# MCU089B_XDS110_MCU.net
KiCad netlist of a schematic drawn in Altium Designer
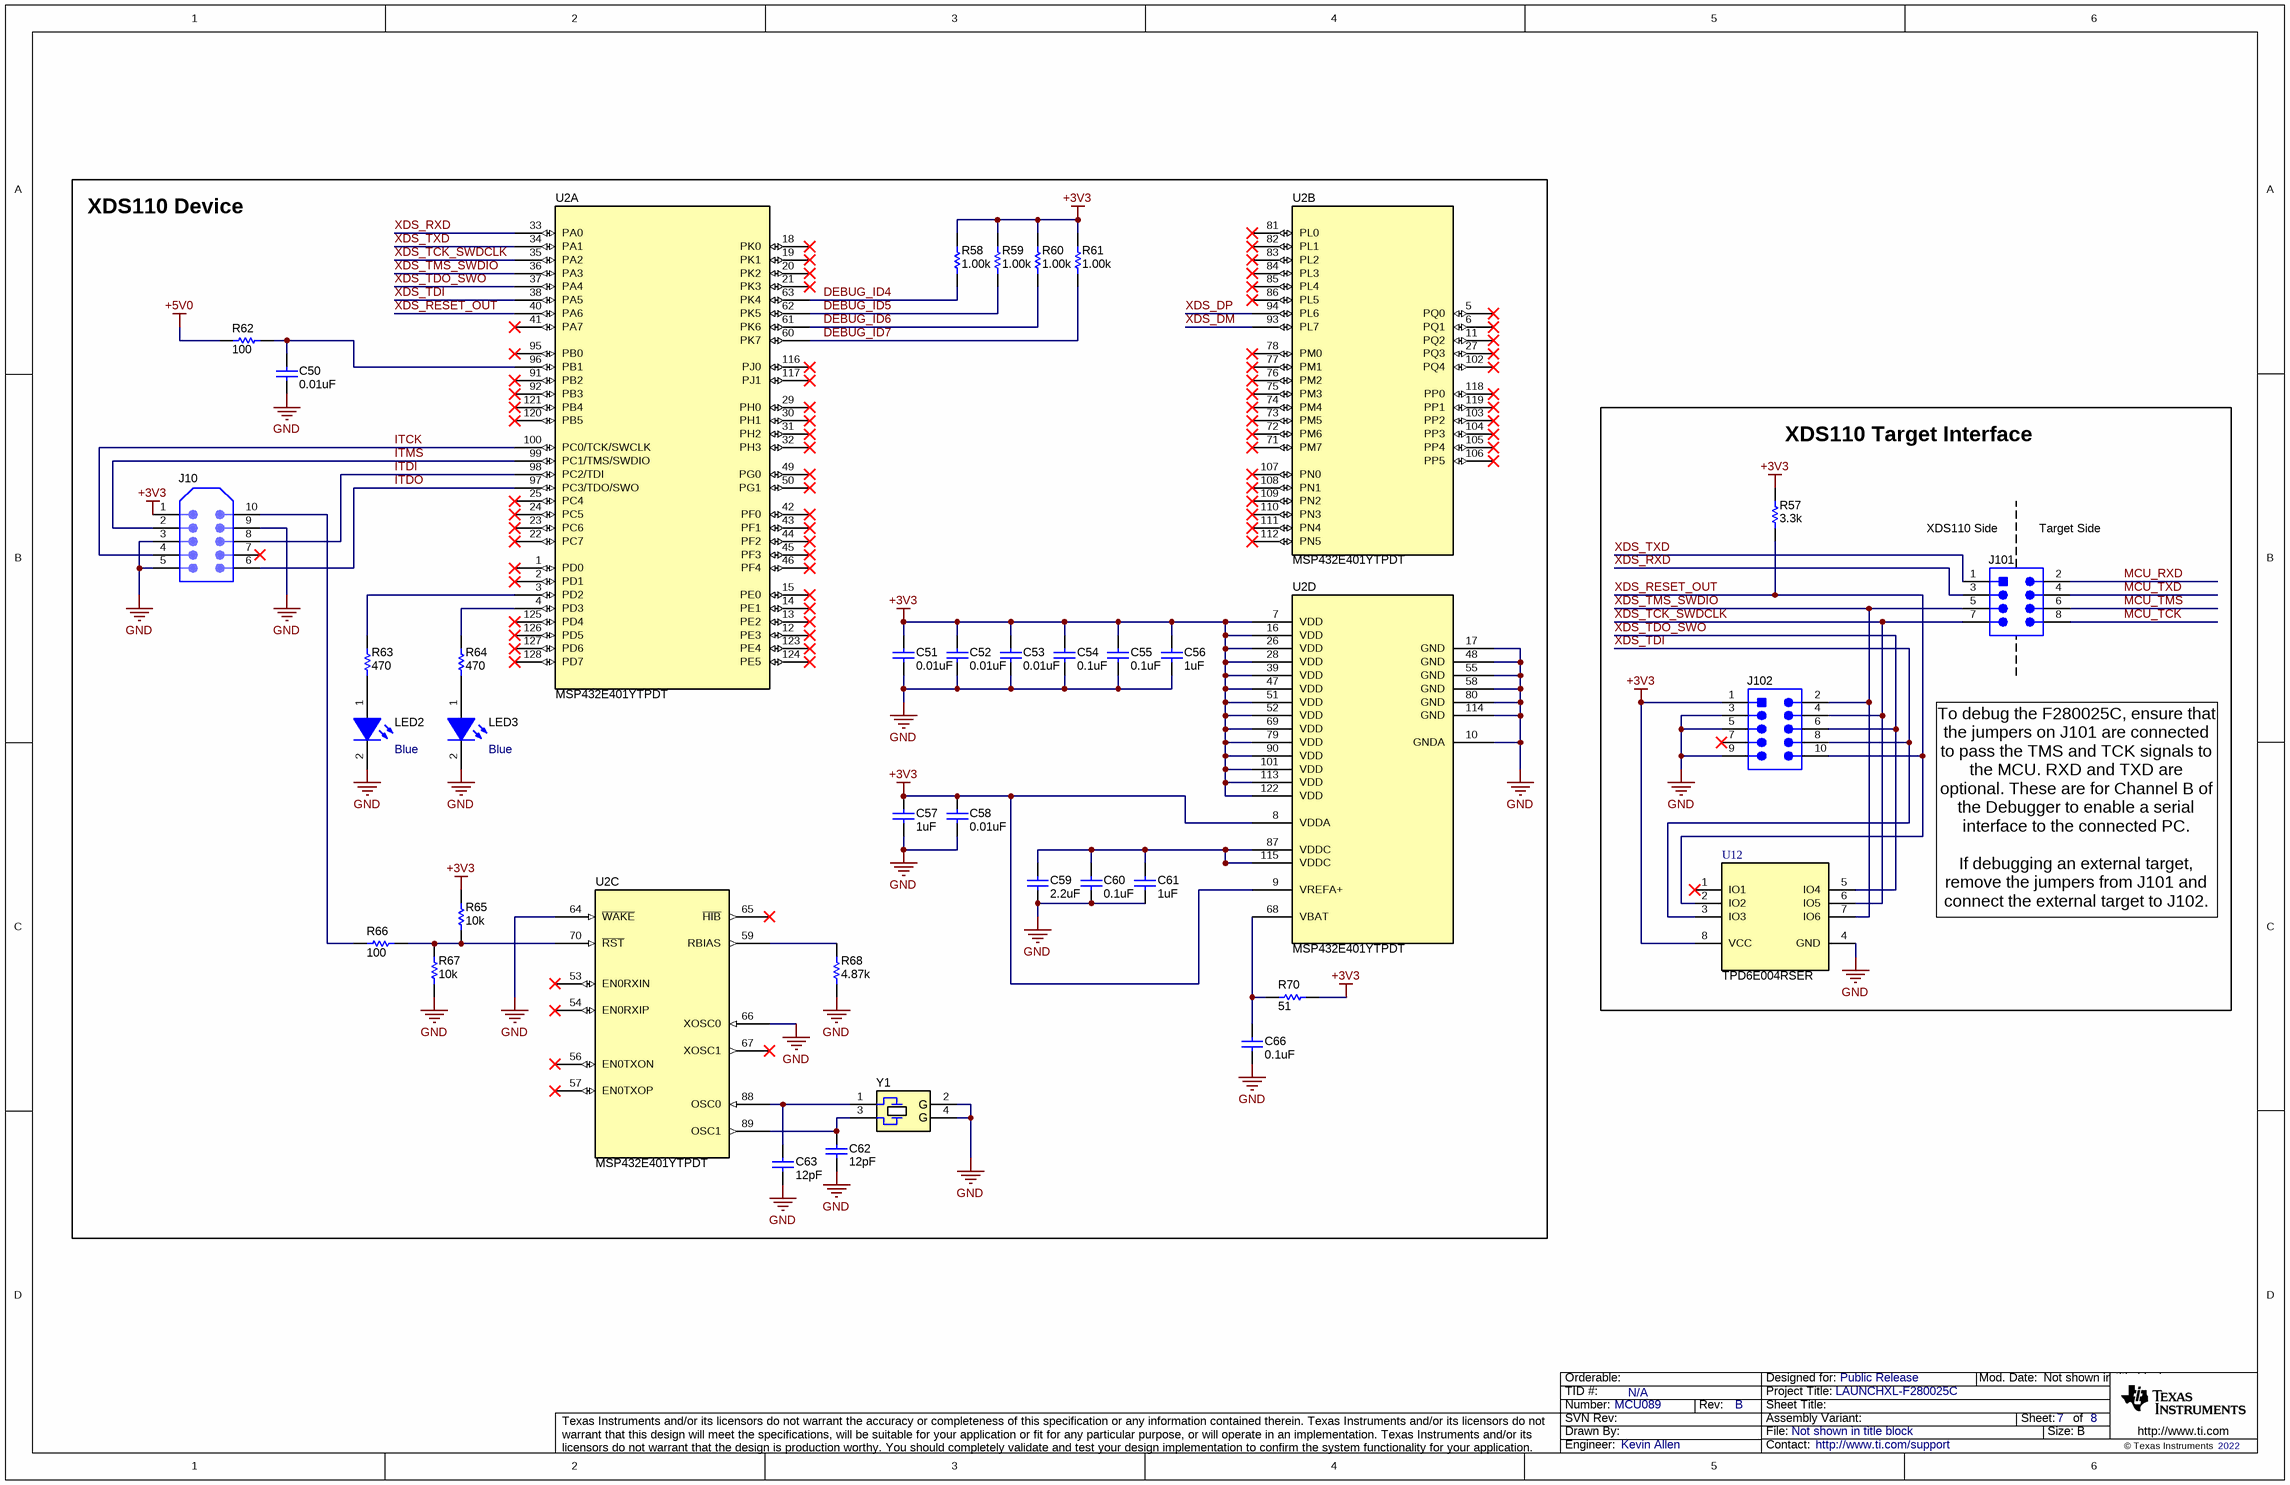
[diagram p0: MCU089B_XDS110_MCU.SchDoc]

(export (version "E")
  (design (tool "Eeschema 10.0.6"))
  (components
    (comp (ref "C50")
      (value "GRM155R71E103KA01D")
      (footprint "0402")
      (description "CAP, CERM, 0.01 uF, 25 V, +/- 10%, X7R, 0402")
      (fields
        (field (name "VALUEDISPLAYED") "0.01uF")
        (field (name "MANUFACTURER") "MuRata")
        (field (name "PUBLISHER") "Texas Instruments")
      )
      (libsource (lib "Altium Vault - TI") (part "Capacitor"))
    )
    (comp (ref "C51")
      (value "GRM155R71E103KA01D")
      (footprint "0402")
      (description "CAP, CERM, 0.01 uF, 25 V, +/- 10%, X7R, 0402")
      (fields
        (field (name "VALUEDISPLAYED") "0.01uF")
        (field (name "MANUFACTURER") "MuRata")
        (field (name "PUBLISHER") "Texas Instruments")
      )
      (libsource (lib "Altium Vault - TI") (part "Capacitor"))
    )
    (comp (ref "C52")
      (value "GRM155R71E103KA01D")
      (footprint "0402")
      (description "CAP, CERM, 0.01 uF, 25 V, +/- 10%, X7R, 0402")
      (fields
        (field (name "VALUEDISPLAYED") "0.01uF")
        (field (name "MANUFACTURER") "MuRata")
        (field (name "PUBLISHER") "Texas Instruments")
      )
      (libsource (lib "Altium Vault - TI") (part "Capacitor"))
    )
    (comp (ref "C53")
      (value "GRM155R71E103KA01D")
      (footprint "0402")
      (description "CAP, CERM, 0.01 uF, 25 V, +/- 10%, X7R, 0402")
      (fields
        (field (name "VALUEDISPLAYED") "0.01uF")
        (field (name "MANUFACTURER") "MuRata")
        (field (name "PUBLISHER") "Texas Instruments")
      )
      (libsource (lib "Altium Vault - TI") (part "Capacitor"))
    )
    (comp (ref "C54")
      (value "GRM155R70J104KA01D")
      (footprint "0402")
      (description "CAP, CERM, 0.1 uF, 6.3 V, +/- 10%, X7R, 0402")
      (fields
        (field (name "VALUEDISPLAYED") "0.1uF")
        (field (name "MANUFACTURER") "MuRata")
        (field (name "PUBLISHER") "Texas Instruments")
      )
      (libsource (lib "Altium Vault - TI") (part "Capacitor"))
    )
    (comp (ref "C55")
      (value "GRM155R70J104KA01D")
      (footprint "0402")
      (description "CAP, CERM, 0.1 uF, 6.3 V, +/- 10%, X7R, 0402")
      (fields
        (field (name "VALUEDISPLAYED") "0.1uF")
        (field (name "MANUFACTURER") "MuRata")
        (field (name "PUBLISHER") "Texas Instruments")
      )
      (libsource (lib "Altium Vault - TI") (part "Capacitor"))
    )
    (comp (ref "C56")
      (value "885012105012")
      (footprint "0402")
      (description "CAP, CERM, 1 uF, 10 V,+/- 20%, X5R, 0402")
      (fields
        (field (name "VALUEDISPLAYED") "1uF")
        (field (name "MANUFACTURER") "Wurth Elektronik")
        (field (name "PUBLISHER") "Texas Instruments")
      )
      (libsource (lib "Altium Vault - TI") (part "Capacitor"))
    )
    (comp (ref "C57")
      (value "885012105012")
      (footprint "0402")
      (description "CAP, CERM, 1 uF, 10 V,+/- 20%, X5R, 0402")
      (fields
        (field (name "VALUEDISPLAYED") "1uF")
        (field (name "MANUFACTURER") "Wurth Elektronik")
        (field (name "PUBLISHER") "Texas Instruments")
      )
      (libsource (lib "Altium Vault - TI") (part "Capacitor"))
    )
    (comp (ref "C58")
      (value "GRM155R71E103KA01D")
      (footprint "0402")
      (description "CAP, CERM, 0.01 uF, 25 V, +/- 10%, X7R, 0402")
      (fields
        (field (name "VALUEDISPLAYED") "0.01uF")
        (field (name "MANUFACTURER") "MuRata")
        (field (name "PUBLISHER") "Texas Instruments")
      )
      (libsource (lib "Altium Vault - TI") (part "Capacitor"))
    )
    (comp (ref "C59")
      (value "GRM155R60J225KE95D")
      (footprint "0402")
      (description "CAP, CERM, 2.2 uF, 6.3 V, +/- 10%, X5R, 0402")
      (fields
        (field (name "VALUEDISPLAYED") "2.2uF")
        (field (name "MANUFACTURER") "MuRata")
        (field (name "PUBLISHER") "Texas Instruments")
      )
      (libsource (lib "Altium Vault - TI") (part "Capacitor"))
    )
    (comp (ref "C60")
      (value "GRM155R70J104KA01D")
      (footprint "0402")
      (description "CAP, CERM, 0.1 uF, 6.3 V, +/- 10%, X7R, 0402")
      (fields
        (field (name "VALUEDISPLAYED") "0.1uF")
        (field (name "MANUFACTURER") "MuRata")
        (field (name "PUBLISHER") "Texas Instruments")
      )
      (libsource (lib "Altium Vault - TI") (part "Capacitor"))
    )
    (comp (ref "C61")
      (value "885012105012")
      (footprint "0402")
      (description "CAP, CERM, 1 uF, 10 V,+/- 20%, X5R, 0402")
      (fields
        (field (name "VALUEDISPLAYED") "1uF")
        (field (name "MANUFACTURER") "Wurth Elektronik")
        (field (name "PUBLISHER") "Texas Instruments")
      )
      (libsource (lib "Altium Vault - TI") (part "Capacitor"))
    )
    (comp (ref "C62")
      (value "C0402C120J3GACAUTO")
      (footprint "0402")
      (description "CAP, CERM, 12 pF, 25 V, +/- 5%, C0G/NP0, AEC-Q200 Grade 1, 0402")
      (fields
        (field (name "MANUFACTURER") "Kemet")
        (field (name "VALUEDISPLAYED") "12pF")
        (field (name "PUBLISHER") "Texas Instruments")
      )
      (libsource (lib "Altium Vault - TI") (part "Capacitor"))
    )
    (comp (ref "C63")
      (value "C0402C120J3GACAUTO")
      (footprint "0402")
      (description "CAP, CERM, 12 pF, 25 V, +/- 5%, C0G/NP0, AEC-Q200 Grade 1, 0402")
      (fields
        (field (name "MANUFACTURER") "Kemet")
        (field (name "VALUEDISPLAYED") "12pF")
        (field (name "PUBLISHER") "Texas Instruments")
      )
      (libsource (lib "Altium Vault - TI") (part "Capacitor"))
    )
    (comp (ref "C66")
      (value "GRM155R70J104KA01D")
      (footprint "0402")
      (description "CAP, CERM, 0.1 uF, 6.3 V, +/- 10%, X7R, 0402")
      (fields
        (field (name "VALUEDISPLAYED") "0.1uF")
        (field (name "MANUFACTURER") "MuRata")
        (field (name "PUBLISHER") "Texas Instruments")
      )
      (libsource (lib "Altium Vault - TI") (part "Capacitor"))
    )
    (comp (ref "J10")
      (value "TC2050-IDC-NL-FP")
      (footprint "Tag_TC2050-NL")
      (description "Footprint for Tag-Connect TC2050 No-Legs cables")
      (fields (field (name "MANUFACTURER") "Tag-Connect") (field (name "PUBLISHER") "Texas Instruments"))
      (libsource (lib "Altium Vault - TI") (part "CMP-0075101-1"))
    )
    (comp (ref "J101")
      (value "TSW-104-07-G-D")
      (footprint "TSW-104-07-G-D")
      (description "Header, 100mil, 4x2, Gold, TH")
      (fields (field (name "MANUFACTURER") "Samtec"))
      (libsource (lib "Altium Vault - TI") (part "Header_4x2"))
    )
    (comp (ref "J102")
      (value "FTSH-105-01-F-DV-K")
      (footprint "Samtec_FTSH-105-01-x-DV-K")
      (description "Header (Shrouded), 1.27mm, 5x2, Gold, SMT")
      (fields (field (name "MANUFACTURER") "Samtec"))
      (libsource (lib "Altium Vault - TI") (part "Header_5x2"))
    )
    (comp (ref "LED2")
      (value "Blue")
      (footprint "LTST-C170TBKT_Blue")
      (description "LED, Blue, SMD")
      (fields (field (name "PARTNUMBER") "LTST-C170TBKT") (field (name "MANUFACTURER") "Lite-On"))
      (libsource (lib "Altium Vault - TI") (part "LED"))
    )
    (comp (ref "LED3")
      (value "Blue")
      (footprint "LTST-C170TBKT_Blue")
      (description "LED, Blue, SMD")
      (fields (field (name "PARTNUMBER") "LTST-C170TBKT") (field (name "MANUFACTURER") "Lite-On"))
      (libsource (lib "Altium Vault - TI") (part "LED"))
    )
    (comp (ref "R57")
      (value "CRCW04023K30JNED")
      (footprint "0402")
      (description "RES, 3.3 k, 5%, 0.063 W, AEC-Q200 Grade 0, 0402")
      (fields (field (name "VALUEDISPLAYED") "3.3k") (field (name "MANUFACTURER") "Vishay-Dale"))
      (libsource (lib "Altium Vault - TI") (part "Resistor"))
    )
    (comp (ref "R58")
      (value "CRCW04021K00FKED")
      (footprint "0402")
      (description "RES, 1.00 k, 1%, 0.063 W, AEC-Q200 Grade 0, 0402")
      (fields (field (name "MANUFACTURER") "Vishay-Dale") (field (name "VALUEDISPLAYED") "1.00k"))
      (libsource (lib "Altium Vault - TI") (part "Resistor"))
    )
    (comp (ref "R59")
      (value "CRCW04021K00FKED")
      (footprint "0402")
      (description "RES, 1.00 k, 1%, 0.063 W, AEC-Q200 Grade 0, 0402")
      (fields (field (name "MANUFACTURER") "Vishay-Dale") (field (name "VALUEDISPLAYED") "1.00k"))
      (libsource (lib "Altium Vault - TI") (part "Resistor"))
    )
    (comp (ref "R60")
      (value "CRCW04021K00FKED")
      (footprint "0402")
      (description "RES, 1.00 k, 1%, 0.063 W, AEC-Q200 Grade 0, 0402")
      (fields (field (name "MANUFACTURER") "Vishay-Dale") (field (name "VALUEDISPLAYED") "1.00k"))
      (libsource (lib "Altium Vault - TI") (part "Resistor"))
    )
    (comp (ref "R61")
      (value "CRCW04021K00FKED")
      (footprint "0402")
      (description "RES, 1.00 k, 1%, 0.063 W, AEC-Q200 Grade 0, 0402")
      (fields (field (name "MANUFACTURER") "Vishay-Dale") (field (name "VALUEDISPLAYED") "1.00k"))
      (libsource (lib "Altium Vault - TI") (part "Resistor"))
    )
    (comp (ref "R62")
      (value "CRCW0402100RJNED")
      (footprint "0402")
      (description "RES, 100, 5%, 0.063 W, AEC-Q200 Grade 0, 0402")
      (fields (field (name "VALUEDISPLAYED") "100") (field (name "MANUFACTURER") "Vishay-Dale"))
      (libsource (lib "Altium Vault - TI") (part "Resistor"))
    )
    (comp (ref "R63")
      (value "ERJ-2RKF4700X")
      (footprint "0402")
      (description "RES, 470, 1%, 0.1 W, AEC-Q200 Grade 0, 0402")
      (fields
        (field (name "VALUEDISPLAYED") "470")
        (field (name "MANUFACTURER") "Panasonic")
        (field (name "PUBLISHER") "Texas Instruments")
      )
      (libsource (lib "Altium Vault - TI") (part "Resistor"))
    )
    (comp (ref "R64")
      (value "ERJ-2RKF4700X")
      (footprint "0402")
      (description "RES, 470, 1%, 0.1 W, AEC-Q200 Grade 0, 0402")
      (fields
        (field (name "VALUEDISPLAYED") "470")
        (field (name "MANUFACTURER") "Panasonic")
        (field (name "PUBLISHER") "Texas Instruments")
      )
      (libsource (lib "Altium Vault - TI") (part "Resistor"))
    )
    (comp (ref "R65")
      (value "CRCW040210K0JNED")
      (footprint "0402")
      (description "RES, 10 k, 5%, 0.063 W, AEC-Q200 Grade 0, 0402")
      (fields (field (name "VALUEDISPLAYED") "10k") (field (name "MANUFACTURER") "Vishay-Dale"))
      (libsource (lib "Altium Vault - TI") (part "Resistor"))
    )
    (comp (ref "R66")
      (value "CRCW0402100RJNED")
      (footprint "0402")
      (description "RES, 100, 5%, 0.063 W, AEC-Q200 Grade 0, 0402")
      (fields (field (name "VALUEDISPLAYED") "100") (field (name "MANUFACTURER") "Vishay-Dale"))
      (libsource (lib "Altium Vault - TI") (part "Resistor"))
    )
    (comp (ref "R67")
      (value "CRCW040210K0JNED")
      (footprint "0402")
      (description "RES, 10 k, 5%, 0.063 W, AEC-Q200 Grade 0, 0402")
      (fields (field (name "VALUEDISPLAYED") "10k") (field (name "MANUFACTURER") "Vishay-Dale"))
      (libsource (lib "Altium Vault - TI") (part "Resistor"))
    )
    (comp (ref "R68")
      (value "CRCW04024K87FKED")
      (footprint "0402")
      (description "RES, 4.87 k, 1%, 0.063 W, AEC-Q200 Grade 0, 0402")
      (fields (field (name "VALUEDISPLAYED") "4.87k") (field (name "MANUFACTURER") "Vishay-Dale"))
      (libsource (lib "Altium Vault - TI") (part "Resistor"))
    )
    (comp (ref "R70")
      (value "CRCW040251R0JNED")
      (footprint "0402")
      (description "RES, 51, 5%, 0.063 W, AEC-Q200 Grade 0, 0402")
      (fields (field (name "VALUEDISPLAYED") "51") (field (name "MANUFACTURER") "Vishay-Dale"))
      (libsource (lib "Altium Vault - TI") (part "Resistor"))
    )
    (comp (ref "U2")
      (value "MSP432E401YTPDT")
      (footprint "PDT0128A")
      (description "MSP432E401YTPDT, PDT0128A (TQFP-128)")
      (fields
        (field (name "ALTERNATE PARTNUMBER") "MSP432E401YTPDTR")
        (field (name "MANUFACTURER") "Texas Instruments")
        (field (name "PARTNUMBER") "MSP432E401YTPDT")
      )
      (libsource (lib "Altium Vault - TI") (part "MSP432E401YTPDT"))
    )
    (comp (ref "U12")
      (value "TPD6E004RSER")
      (footprint "RSE0008A")
      (fields (field (name "MANUFACTURER") "Texas Instruments") (field (name "PARTNUMBER") "TPD6E004RSER"))
      (libsource (lib "Altium Vault - TI") (part "TI-TPD6E004-UQFN_RSE-8"))
    )
    (comp (ref "Y1")
      (value "NX3225GA-16.000M-STD-CRG-1")
      (footprint "NDK_NX3225GA")
      (description "Crystal, 16 MHz, 8pF, SMD")
      (fields (field (name "MANUFACTURER") "NDK"))
      (libsource (lib "Altium Vault - TI") (part "XTAL_4P_13_G24"))
    )
  )
  (nets
    (net (code "1") (name "+3V3") (class "Default")
      (node (ref "C51") (pin "1") (pinfunction "1_1") (pintype "passive"))
      (node (ref "C52") (pin "1") (pinfunction "1_1") (pintype "passive"))
      (node (ref "C53") (pin "1") (pinfunction "1_1") (pintype "passive"))
      (node (ref "C54") (pin "1") (pinfunction "1_1") (pintype "passive"))
      (node (ref "C55") (pin "1") (pinfunction "1_1") (pintype "passive"))
      (node (ref "C56") (pin "1") (pinfunction "1_1") (pintype "passive"))
      (node (ref "C57") (pin "1") (pinfunction "1_1") (pintype "passive"))
      (node (ref "C58") (pin "1") (pinfunction "1_1") (pintype "passive"))
      (node (ref "J10") (pin "1") (pinfunction "1_1") (pintype "passive"))
      (node (ref "J102") (pin "1") (pinfunction "1_1") (pintype "passive"))
      (node (ref "R57") (pin "2") (pinfunction "2_2") (pintype "passive"))
      (node (ref "R58") (pin "2") (pinfunction "2_2") (pintype "passive"))
      (node (ref "R59") (pin "2") (pinfunction "2_2") (pintype "passive"))
      (node (ref "R60") (pin "2") (pinfunction "2_2") (pintype "passive"))
      (node (ref "R61") (pin "2") (pinfunction "2_2") (pintype "passive"))
      (node (ref "R65") (pin "2") (pinfunction "2_2") (pintype "passive"))
      (node (ref "R70") (pin "2") (pinfunction "2_2") (pintype "passive"))
      (node (ref "U12") (pin "8") (pinfunction "VCC_8") (pintype "power_in"))
      (node (ref "U2") (pin "101") (pinfunction "VDD_101") (pintype "power_in"))
      (node (ref "U2") (pin "113") (pinfunction "VDD_113") (pintype "power_in"))
      (node (ref "U2") (pin "122") (pinfunction "VDD_122") (pintype "power_in"))
      (node (ref "U2") (pin "16") (pinfunction "VDD_16") (pintype "power_in"))
      (node (ref "U2") (pin "26") (pinfunction "VDD_26") (pintype "power_in"))
      (node (ref "U2") (pin "28") (pinfunction "VDD_28") (pintype "power_in"))
      (node (ref "U2") (pin "39") (pinfunction "VDD_39") (pintype "power_in"))
      (node (ref "U2") (pin "47") (pinfunction "VDD_47") (pintype "power_in"))
      (node (ref "U2") (pin "51") (pinfunction "VDD_51") (pintype "power_in"))
      (node (ref "U2") (pin "52") (pinfunction "VDD_52") (pintype "power_in"))
      (node (ref "U2") (pin "69") (pinfunction "VDD_69") (pintype "power_in"))
      (node (ref "U2") (pin "7") (pinfunction "VDD_7") (pintype "power_in"))
      (node (ref "U2") (pin "79") (pinfunction "VDD_79") (pintype "power_in"))
      (node (ref "U2") (pin "8") (pinfunction "VDDA_8") (pintype "power_in"))
      (node (ref "U2") (pin "9") (pinfunction "VREFA+_9") (pintype "power_in"))
      (node (ref "U2") (pin "90") (pinfunction "VDD_90") (pintype "power_in"))
    )
    (net (code "2") (name "+5V0") (class "Default")
      (node (ref "R62") (pin "1") (pinfunction "1_1") (pintype "passive"))
    )
    (net (code "3") (name "/DEBUG_ID4") (class "Default")
      (node (ref "R58") (pin "1") (pinfunction "1_1") (pintype "passive"))
      (node (ref "U2") (pin "63") (pinfunction "PK4_63") (pintype "bidirectional"))
    )
    (net (code "4") (name "/DEBUG_ID5") (class "Default")
      (node (ref "R59") (pin "1") (pinfunction "1_1") (pintype "passive"))
      (node (ref "U2") (pin "62") (pinfunction "PK5_62") (pintype "bidirectional"))
    )
    (net (code "5") (name "/DEBUG_ID6") (class "Default")
      (node (ref "R60") (pin "1") (pinfunction "1_1") (pintype "passive"))
      (node (ref "U2") (pin "61") (pinfunction "PK6_61") (pintype "bidirectional"))
    )
    (net (code "6") (name "/DEBUG_ID7") (class "Default")
      (node (ref "R61") (pin "1") (pinfunction "1_1") (pintype "passive"))
      (node (ref "U2") (pin "60") (pinfunction "PK7_60") (pintype "bidirectional"))
    )
    (net (code "7") (name "/ITCK") (class "Default")
      (node (ref "J10") (pin "4") (pinfunction "4_4") (pintype "passive"))
      (node (ref "U2") (pin "100") (pinfunction "PC0/TCK/SWCLK_100") (pintype "bidirectional"))
    )
    (net (code "8") (name "/ITDI") (class "Default")
      (node (ref "J10") (pin "8") (pinfunction "8_8") (pintype "passive"))
      (node (ref "U2") (pin "98") (pinfunction "PC2/TDI_98") (pintype "bidirectional"))
    )
    (net (code "9") (name "/ITDO") (class "Default")
      (node (ref "J10") (pin "6") (pinfunction "6_6") (pintype "passive"))
      (node (ref "U2") (pin "97") (pinfunction "PC3/TDO/SWO_97") (pintype "bidirectional"))
    )
    (net (code "10") (name "/ITMS") (class "Default")
      (node (ref "J10") (pin "2") (pinfunction "2_2") (pintype "passive"))
      (node (ref "U2") (pin "99") (pinfunction "PC1/TMS/SWDIO_99") (pintype "bidirectional"))
    )
    (net (code "11") (name "/MCU_RXD") (class "Default")
      (node (ref "J101") (pin "2") (pinfunction "2_2") (pintype "passive"))
    )
    (net (code "12") (name "/MCU_TCK") (class "Default")
      (node (ref "J101") (pin "8") (pinfunction "8_8") (pintype "passive"))
    )
    (net (code "13") (name "/MCU_TMS") (class "Default")
      (node (ref "J101") (pin "6") (pinfunction "6_6") (pintype "passive"))
    )
    (net (code "14") (name "/MCU_TXD") (class "Default")
      (node (ref "J101") (pin "4") (pinfunction "4_4") (pintype "passive"))
    )
    (net (code "15") (name "/XDS_DM") (class "Default")
      (node (ref "U2") (pin "93") (pinfunction "PL7_93") (pintype "bidirectional"))
    )
    (net (code "16") (name "/XDS_DP") (class "Default")
      (node (ref "U2") (pin "94") (pinfunction "PL6_94") (pintype "bidirectional"))
    )
    (net (code "17") (name "/XDS_RESET_OUT") (class "Default")
      (node (ref "J102") (pin "10") (pinfunction "10_10") (pintype "passive"))
      (node (ref "R57") (pin "1") (pinfunction "1_1") (pintype "passive"))
      (node (ref "U12") (pin "2") (pinfunction "IO2_2") (pintype "passive"))
      (node (ref "U2") (pin "40") (pinfunction "PA6_40") (pintype "bidirectional"))
    )
    (net (code "18") (name "/XDS_RXD") (class "Default")
      (node (ref "J101") (pin "3") (pinfunction "3_3") (pintype "passive"))
      (node (ref "U2") (pin "33") (pinfunction "PA0_33") (pintype "bidirectional"))
    )
    (net (code "19") (name "/XDS_TCK_SWDCLK") (class "Default")
      (node (ref "J101") (pin "7") (pinfunction "7_7") (pintype "passive"))
      (node (ref "J102") (pin "4") (pinfunction "4_4") (pintype "passive"))
      (node (ref "U12") (pin "6") (pinfunction "IO5_6") (pintype "passive"))
      (node (ref "U2") (pin "35") (pinfunction "PA2_35") (pintype "bidirectional"))
    )
    (net (code "20") (name "/XDS_TDI") (class "Default")
      (node (ref "J102") (pin "8") (pinfunction "8_8") (pintype "passive"))
      (node (ref "U12") (pin "3") (pinfunction "IO3_3") (pintype "passive"))
      (node (ref "U2") (pin "38") (pinfunction "PA5_38") (pintype "bidirectional"))
    )
    (net (code "21") (name "/XDS_TDO_SWO") (class "Default")
      (node (ref "J102") (pin "6") (pinfunction "6_6") (pintype "passive"))
      (node (ref "U12") (pin "5") (pinfunction "IO4_5") (pintype "passive"))
      (node (ref "U2") (pin "37") (pinfunction "PA4_37") (pintype "bidirectional"))
    )
    (net (code "22") (name "/XDS_TMS_SWDIO") (class "Default")
      (node (ref "J101") (pin "5") (pinfunction "5_5") (pintype "passive"))
      (node (ref "J102") (pin "2") (pinfunction "2_2") (pintype "passive"))
      (node (ref "U12") (pin "7") (pinfunction "IO6_7") (pintype "passive"))
      (node (ref "U2") (pin "36") (pinfunction "PA3_36") (pintype "bidirectional"))
    )
    (net (code "23") (name "/XDS_TXD") (class "Default")
      (node (ref "J101") (pin "1") (pinfunction "1_1") (pintype "passive"))
      (node (ref "U2") (pin "34") (pinfunction "PA1_34") (pintype "bidirectional"))
    )
    (net (code "24") (name "GND") (class "Default")
      (node (ref "C50") (pin "2") (pinfunction "2_2") (pintype "passive"))
      (node (ref "C51") (pin "2") (pinfunction "2_2") (pintype "passive"))
      (node (ref "C52") (pin "2") (pinfunction "2_2") (pintype "passive"))
      (node (ref "C53") (pin "2") (pinfunction "2_2") (pintype "passive"))
      (node (ref "C54") (pin "2") (pinfunction "2_2") (pintype "passive"))
      (node (ref "C55") (pin "2") (pinfunction "2_2") (pintype "passive"))
      (node (ref "C56") (pin "2") (pinfunction "2_2") (pintype "passive"))
      (node (ref "C57") (pin "2") (pinfunction "2_2") (pintype "passive"))
      (node (ref "C58") (pin "2") (pinfunction "2_2") (pintype "passive"))
      (node (ref "C59") (pin "2") (pinfunction "2_2") (pintype "passive"))
      (node (ref "C60") (pin "2") (pinfunction "2_2") (pintype "passive"))
      (node (ref "C61") (pin "2") (pinfunction "2_2") (pintype "passive"))
      (node (ref "C62") (pin "2") (pinfunction "2_2") (pintype "passive"))
      (node (ref "C63") (pin "2") (pinfunction "2_2") (pintype "passive"))
      (node (ref "C66") (pin "2") (pinfunction "2_2") (pintype "passive"))
      (node (ref "J10") (pin "3") (pinfunction "3_3") (pintype "passive"))
      (node (ref "J10") (pin "5") (pinfunction "5_5") (pintype "passive"))
      (node (ref "J10") (pin "9") (pinfunction "9_9") (pintype "passive"))
      (node (ref "J102") (pin "3") (pinfunction "3_3") (pintype "passive"))
      (node (ref "J102") (pin "5") (pinfunction "5_5") (pintype "passive"))
      (node (ref "J102") (pin "9") (pinfunction "9_9") (pintype "passive"))
      (node (ref "LED2") (pin "2") (pinfunction "K_2") (pintype "passive"))
      (node (ref "LED3") (pin "2") (pinfunction "K_2") (pintype "passive"))
      (node (ref "R67") (pin "1") (pinfunction "1_1") (pintype "passive"))
      (node (ref "R68") (pin "1") (pinfunction "1_1") (pintype "passive"))
      (node (ref "U12") (pin "4") (pinfunction "GND_4") (pintype "power_in"))
      (node (ref "U2") (pin "10") (pinfunction "GNDA_10") (pintype "power_in"))
      (node (ref "U2") (pin "114") (pinfunction "GND_114") (pintype "power_in"))
      (node (ref "U2") (pin "17") (pinfunction "GND_17") (pintype "power_in"))
      (node (ref "U2") (pin "48") (pinfunction "GND_48") (pintype "power_in"))
      (node (ref "U2") (pin "55") (pinfunction "GND_55") (pintype "power_in"))
      (node (ref "U2") (pin "58") (pinfunction "GND_58") (pintype "power_in"))
      (node (ref "U2") (pin "64") (pinfunction "WAKE_64") (pintype "input"))
      (node (ref "U2") (pin "66") (pinfunction "XOSC0_66") (pintype "input"))
      (node (ref "U2") (pin "80") (pinfunction "GND_80") (pintype "power_in"))
      (node (ref "Y1") (pin "2") (pinfunction "GND_2") (pintype "power_in"))
      (node (ref "Y1") (pin "4") (pinfunction "GND_4") (pintype "power_in"))
    )
    (net (code "25") (name "Net-(C59-Pad1)") (class "Default")
      (node (ref "C59") (pin "1") (pinfunction "1_1") (pintype "passive"))
      (node (ref "C60") (pin "1") (pinfunction "1_1") (pintype "passive"))
      (node (ref "C61") (pin "1") (pinfunction "1_1") (pintype "passive"))
      (node (ref "U2") (pin "115") (pinfunction "VDDC_115") (pintype "power_in"))
      (node (ref "U2") (pin "87") (pinfunction "VDDC_87") (pintype "power_in"))
    )
    (net (code "26") (name "Net-(J10-Pad10)") (class "Default")
      (node (ref "J10") (pin "10") (pinfunction "10_10") (pintype "passive"))
      (node (ref "R66") (pin "1") (pinfunction "1_1") (pintype "passive"))
    )
    (net (code "27") (name "Net-(LED2-A)") (class "Default")
      (node (ref "LED2") (pin "1") (pinfunction "A_1") (pintype "passive"))
      (node (ref "R63") (pin "1") (pinfunction "1_1") (pintype "passive"))
    )
    (net (code "28") (name "Net-(LED3-A)") (class "Default")
      (node (ref "LED3") (pin "1") (pinfunction "A_1") (pintype "passive"))
      (node (ref "R64") (pin "1") (pinfunction "1_1") (pintype "passive"))
    )
    (net (code "29") (name "Net-(U2A-PB1)") (class "Default")
      (node (ref "C50") (pin "1") (pinfunction "1_1") (pintype "passive"))
      (node (ref "R62") (pin "2") (pinfunction "2_2") (pintype "passive"))
      (node (ref "U2") (pin "96") (pinfunction "PB1_96") (pintype "bidirectional"))
    )
    (net (code "30") (name "Net-(U2A-PD2)") (class "Default")
      (node (ref "R63") (pin "2") (pinfunction "2_2") (pintype "passive"))
      (node (ref "U2") (pin "3") (pinfunction "PD2_3") (pintype "bidirectional"))
    )
    (net (code "31") (name "Net-(U2A-PD3)") (class "Default")
      (node (ref "R64") (pin "2") (pinfunction "2_2") (pintype "passive"))
      (node (ref "U2") (pin "4") (pinfunction "PD3_4") (pintype "bidirectional"))
    )
    (net (code "32") (name "Net-(U2C-OSC0)") (class "Default")
      (node (ref "C63") (pin "1") (pinfunction "1_1") (pintype "passive"))
      (node (ref "U2") (pin "88") (pinfunction "OSC0_88") (pintype "input"))
      (node (ref "Y1") (pin "1") (pinfunction "1_1") (pintype "passive"))
    )
    (net (code "33") (name "Net-(U2C-OSC1)") (class "Default")
      (node (ref "C62") (pin "1") (pinfunction "1_1") (pintype "passive"))
      (node (ref "U2") (pin "89") (pinfunction "OSC1_89") (pintype "output"))
      (node (ref "Y1") (pin "3") (pinfunction "3_3") (pintype "passive"))
    )
    (net (code "34") (name "Net-(U2C-RBIAS)") (class "Default")
      (node (ref "R68") (pin "2") (pinfunction "2_2") (pintype "passive"))
      (node (ref "U2") (pin "59") (pinfunction "RBIAS_59") (pintype "output"))
    )
    (net (code "35") (name "Net-(U2C-RST)") (class "Default")
      (node (ref "R65") (pin "1") (pinfunction "1_1") (pintype "passive"))
      (node (ref "R66") (pin "2") (pinfunction "2_2") (pintype "passive"))
      (node (ref "R67") (pin "2") (pinfunction "2_2") (pintype "passive"))
      (node (ref "U2") (pin "70") (pinfunction "RST_70") (pintype "input"))
    )
    (net (code "36") (name "Net-(U2D-VBAT)") (class "Default")
      (node (ref "C66") (pin "1") (pinfunction "1_1") (pintype "passive"))
      (node (ref "R70") (pin "1") (pinfunction "1_1") (pintype "passive"))
      (node (ref "U2") (pin "68") (pinfunction "VBAT_68") (pintype "power_in"))
    )
    (net (code "37") (name "unconnected-(J10-Pad7)") (class "Default")
      (node (ref "J10") (pin "7") (pinfunction "7_7") (pintype "passive+no_connect"))
    )
    (net (code "38") (name "unconnected-(J102-Pad7)") (class "Default")
      (node (ref "J102") (pin "7") (pinfunction "7_7") (pintype "passive+no_connect"))
    )
    (net (code "39") (name "unconnected-(U2A-PA7-Pad41)") (class "Default")
      (node (ref "U2") (pin "41") (pinfunction "PA7_41") (pintype "bidirectional+no_connect"))
    )
    (net (code "40") (name "unconnected-(U2A-PB0-Pad95)") (class "Default")
      (node (ref "U2") (pin "95") (pinfunction "PB0_95") (pintype "bidirectional+no_connect"))
    )
    (net (code "41") (name "unconnected-(U2A-PB2-Pad91)") (class "Default")
      (node (ref "U2") (pin "91") (pinfunction "PB2_91") (pintype "bidirectional+no_connect"))
    )
    (net (code "42") (name "unconnected-(U2A-PB3-Pad92)") (class "Default")
      (node (ref "U2") (pin "92") (pinfunction "PB3_92") (pintype "bidirectional+no_connect"))
    )
    (net (code "43") (name "unconnected-(U2A-PB4-Pad121)") (class "Default")
      (node (ref "U2") (pin "121") (pinfunction "PB4_121") (pintype "bidirectional+no_connect"))
    )
    (net (code "44") (name "unconnected-(U2A-PB5-Pad120)") (class "Default")
      (node (ref "U2") (pin "120") (pinfunction "PB5_120") (pintype "bidirectional+no_connect"))
    )
    (net (code "45") (name "unconnected-(U2A-PC4-Pad25)") (class "Default")
      (node (ref "U2") (pin "25") (pinfunction "PC4_25") (pintype "bidirectional+no_connect"))
    )
    (net (code "46") (name "unconnected-(U2A-PC5-Pad24)") (class "Default")
      (node (ref "U2") (pin "24") (pinfunction "PC5_24") (pintype "bidirectional+no_connect"))
    )
    (net (code "47") (name "unconnected-(U2A-PC6-Pad23)") (class "Default")
      (node (ref "U2") (pin "23") (pinfunction "PC6_23") (pintype "bidirectional+no_connect"))
    )
    (net (code "48") (name "unconnected-(U2A-PC7-Pad22)") (class "Default")
      (node (ref "U2") (pin "22") (pinfunction "PC7_22") (pintype "bidirectional+no_connect"))
    )
    (net (code "49") (name "unconnected-(U2A-PD0-Pad1)") (class "Default")
      (node (ref "U2") (pin "1") (pinfunction "PD0_1") (pintype "bidirectional+no_connect"))
    )
    (net (code "50") (name "unconnected-(U2A-PD1-Pad2)") (class "Default")
      (node (ref "U2") (pin "2") (pinfunction "PD1_2") (pintype "bidirectional+no_connect"))
    )
    (net (code "51") (name "unconnected-(U2A-PD4-Pad125)") (class "Default")
      (node (ref "U2") (pin "125") (pinfunction "PD4_125") (pintype "bidirectional+no_connect"))
    )
    (net (code "52") (name "unconnected-(U2A-PD5-Pad126)") (class "Default")
      (node (ref "U2") (pin "126") (pinfunction "PD5_126") (pintype "bidirectional+no_connect"))
    )
    (net (code "53") (name "unconnected-(U2A-PD6-Pad127)") (class "Default")
      (node (ref "U2") (pin "127") (pinfunction "PD6_127") (pintype "bidirectional+no_connect"))
    )
    (net (code "54") (name "unconnected-(U2A-PD7-Pad128)") (class "Default")
      (node (ref "U2") (pin "128") (pinfunction "PD7_128") (pintype "bidirectional+no_connect"))
    )
    (net (code "55") (name "unconnected-(U2A-PE0-Pad15)") (class "Default")
      (node (ref "U2") (pin "15") (pinfunction "PE0_15") (pintype "bidirectional+no_connect"))
    )
    (net (code "56") (name "unconnected-(U2A-PE1-Pad14)") (class "Default")
      (node (ref "U2") (pin "14") (pinfunction "PE1_14") (pintype "bidirectional+no_connect"))
    )
    (net (code "57") (name "unconnected-(U2A-PE2-Pad13)") (class "Default")
      (node (ref "U2") (pin "13") (pinfunction "PE2_13") (pintype "bidirectional+no_connect"))
    )
    (net (code "58") (name "unconnected-(U2A-PE3-Pad12)") (class "Default")
      (node (ref "U2") (pin "12") (pinfunction "PE3_12") (pintype "bidirectional+no_connect"))
    )
    (net (code "59") (name "unconnected-(U2A-PE4-Pad123)") (class "Default")
      (node (ref "U2") (pin "123") (pinfunction "PE4_123") (pintype "bidirectional+no_connect"))
    )
    (net (code "60") (name "unconnected-(U2A-PE5-Pad124)") (class "Default")
      (node (ref "U2") (pin "124") (pinfunction "PE5_124") (pintype "bidirectional+no_connect"))
    )
    (net (code "61") (name "unconnected-(U2A-PF0-Pad42)") (class "Default")
      (node (ref "U2") (pin "42") (pinfunction "PF0_42") (pintype "bidirectional+no_connect"))
    )
    (net (code "62") (name "unconnected-(U2A-PF1-Pad43)") (class "Default")
      (node (ref "U2") (pin "43") (pinfunction "PF1_43") (pintype "bidirectional+no_connect"))
    )
    (net (code "63") (name "unconnected-(U2A-PF2-Pad44)") (class "Default")
      (node (ref "U2") (pin "44") (pinfunction "PF2_44") (pintype "bidirectional+no_connect"))
    )
    (net (code "64") (name "unconnected-(U2A-PF3-Pad45)") (class "Default")
      (node (ref "U2") (pin "45") (pinfunction "PF3_45") (pintype "bidirectional+no_connect"))
    )
    (net (code "65") (name "unconnected-(U2A-PF4-Pad46)") (class "Default")
      (node (ref "U2") (pin "46") (pinfunction "PF4_46") (pintype "bidirectional+no_connect"))
    )
    (net (code "66") (name "unconnected-(U2A-PG0-Pad49)") (class "Default")
      (node (ref "U2") (pin "49") (pinfunction "PG0_49") (pintype "bidirectional+no_connect"))
    )
    (net (code "67") (name "unconnected-(U2A-PG1-Pad50)") (class "Default")
      (node (ref "U2") (pin "50") (pinfunction "PG1_50") (pintype "bidirectional+no_connect"))
    )
    (net (code "68") (name "unconnected-(U2A-PH0-Pad29)") (class "Default")
      (node (ref "U2") (pin "29") (pinfunction "PH0_29") (pintype "bidirectional+no_connect"))
    )
    (net (code "69") (name "unconnected-(U2A-PH1-Pad30)") (class "Default")
      (node (ref "U2") (pin "30") (pinfunction "PH1_30") (pintype "bidirectional+no_connect"))
    )
    (net (code "70") (name "unconnected-(U2A-PH2-Pad31)") (class "Default")
      (node (ref "U2") (pin "31") (pinfunction "PH2_31") (pintype "bidirectional+no_connect"))
    )
    (net (code "71") (name "unconnected-(U2A-PH3-Pad32)") (class "Default")
      (node (ref "U2") (pin "32") (pinfunction "PH3_32") (pintype "bidirectional+no_connect"))
    )
    (net (code "72") (name "unconnected-(U2A-PJ0-Pad116)") (class "Default")
      (node (ref "U2") (pin "116") (pinfunction "PJ0_116") (pintype "bidirectional+no_connect"))
    )
    (net (code "73") (name "unconnected-(U2A-PJ1-Pad117)") (class "Default")
      (node (ref "U2") (pin "117") (pinfunction "PJ1_117") (pintype "bidirectional+no_connect"))
    )
    (net (code "74") (name "unconnected-(U2A-PK0-Pad18)") (class "Default")
      (node (ref "U2") (pin "18") (pinfunction "PK0_18") (pintype "bidirectional+no_connect"))
    )
    (net (code "75") (name "unconnected-(U2A-PK1-Pad19)") (class "Default")
      (node (ref "U2") (pin "19") (pinfunction "PK1_19") (pintype "bidirectional+no_connect"))
    )
    (net (code "76") (name "unconnected-(U2A-PK2-Pad20)") (class "Default")
      (node (ref "U2") (pin "20") (pinfunction "PK2_20") (pintype "bidirectional+no_connect"))
    )
    (net (code "77") (name "unconnected-(U2A-PK3-Pad21)") (class "Default")
      (node (ref "U2") (pin "21") (pinfunction "PK3_21") (pintype "bidirectional+no_connect"))
    )
    (net (code "78") (name "unconnected-(U2B-PL0-Pad81)") (class "Default")
      (node (ref "U2") (pin "81") (pinfunction "PL0_81") (pintype "bidirectional+no_connect"))
    )
    (net (code "79") (name "unconnected-(U2B-PL1-Pad82)") (class "Default")
      (node (ref "U2") (pin "82") (pinfunction "PL1_82") (pintype "bidirectional+no_connect"))
    )
    (net (code "80") (name "unconnected-(U2B-PL2-Pad83)") (class "Default")
      (node (ref "U2") (pin "83") (pinfunction "PL2_83") (pintype "bidirectional+no_connect"))
    )
    (net (code "81") (name "unconnected-(U2B-PL3-Pad84)") (class "Default")
      (node (ref "U2") (pin "84") (pinfunction "PL3_84") (pintype "bidirectional+no_connect"))
    )
    (net (code "82") (name "unconnected-(U2B-PL4-Pad85)") (class "Default")
      (node (ref "U2") (pin "85") (pinfunction "PL4_85") (pintype "bidirectional+no_connect"))
    )
    (net (code "83") (name "unconnected-(U2B-PL5-Pad86)") (class "Default")
      (node (ref "U2") (pin "86") (pinfunction "PL5_86") (pintype "bidirectional+no_connect"))
    )
    (net (code "84") (name "unconnected-(U2B-PM0-Pad78)") (class "Default")
      (node (ref "U2") (pin "78") (pinfunction "PM0_78") (pintype "bidirectional+no_connect"))
    )
    (net (code "85") (name "unconnected-(U2B-PM1-Pad77)") (class "Default")
      (node (ref "U2") (pin "77") (pinfunction "PM1_77") (pintype "bidirectional+no_connect"))
    )
    (net (code "86") (name "unconnected-(U2B-PM2-Pad76)") (class "Default")
      (node (ref "U2") (pin "76") (pinfunction "PM2_76") (pintype "bidirectional+no_connect"))
    )
    (net (code "87") (name "unconnected-(U2B-PM3-Pad75)") (class "Default")
      (node (ref "U2") (pin "75") (pinfunction "PM3_75") (pintype "bidirectional+no_connect"))
    )
    (net (code "88") (name "unconnected-(U2B-PM4-Pad74)") (class "Default")
      (node (ref "U2") (pin "74") (pinfunction "PM4_74") (pintype "bidirectional+no_connect"))
    )
    (net (code "89") (name "unconnected-(U2B-PM5-Pad73)") (class "Default")
      (node (ref "U2") (pin "73") (pinfunction "PM5_73") (pintype "bidirectional+no_connect"))
    )
    (net (code "90") (name "unconnected-(U2B-PM6-Pad72)") (class "Default")
      (node (ref "U2") (pin "72") (pinfunction "PM6_72") (pintype "bidirectional+no_connect"))
    )
    (net (code "91") (name "unconnected-(U2B-PM7-Pad71)") (class "Default")
      (node (ref "U2") (pin "71") (pinfunction "PM7_71") (pintype "bidirectional+no_connect"))
    )
    (net (code "92") (name "unconnected-(U2B-PN0-Pad107)") (class "Default")
      (node (ref "U2") (pin "107") (pinfunction "PN0_107") (pintype "bidirectional+no_connect"))
    )
    (net (code "93") (name "unconnected-(U2B-PN1-Pad108)") (class "Default")
      (node (ref "U2") (pin "108") (pinfunction "PN1_108") (pintype "bidirectional+no_connect"))
    )
    (net (code "94") (name "unconnected-(U2B-PN2-Pad109)") (class "Default")
      (node (ref "U2") (pin "109") (pinfunction "PN2_109") (pintype "bidirectional+no_connect"))
    )
    (net (code "95") (name "unconnected-(U2B-PN3-Pad110)") (class "Default")
      (node (ref "U2") (pin "110") (pinfunction "PN3_110") (pintype "bidirectional+no_connect"))
    )
    (net (code "96") (name "unconnected-(U2B-PN4-Pad111)") (class "Default")
      (node (ref "U2") (pin "111") (pinfunction "PN4_111") (pintype "bidirectional+no_connect"))
    )
    (net (code "97") (name "unconnected-(U2B-PN5-Pad112)") (class "Default")
      (node (ref "U2") (pin "112") (pinfunction "PN5_112") (pintype "bidirectional+no_connect"))
    )
    (net (code "98") (name "unconnected-(U2B-PP0-Pad118)") (class "Default")
      (node (ref "U2") (pin "118") (pinfunction "PP0_118") (pintype "bidirectional+no_connect"))
    )
    (net (code "99") (name "unconnected-(U2B-PP1-Pad119)") (class "Default")
      (node (ref "U2") (pin "119") (pinfunction "PP1_119") (pintype "bidirectional+no_connect"))
    )
    (net (code "100") (name "unconnected-(U2B-PP2-Pad103)") (class "Default")
      (node (ref "U2") (pin "103") (pinfunction "PP2_103") (pintype "bidirectional+no_connect"))
    )
    (net (code "101") (name "unconnected-(U2B-PP3-Pad104)") (class "Default")
      (node (ref "U2") (pin "104") (pinfunction "PP3_104") (pintype "bidirectional+no_connect"))
    )
    (net (code "102") (name "unconnected-(U2B-PP4-Pad105)") (class "Default")
      (node (ref "U2") (pin "105") (pinfunction "PP4_105") (pintype "bidirectional+no_connect"))
    )
    (net (code "103") (name "unconnected-(U2B-PP5-Pad106)") (class "Default")
      (node (ref "U2") (pin "106") (pinfunction "PP5_106") (pintype "bidirectional+no_connect"))
    )
    (net (code "104") (name "unconnected-(U2B-PQ0-Pad5)") (class "Default")
      (node (ref "U2") (pin "5") (pinfunction "PQ0_5") (pintype "bidirectional+no_connect"))
    )
    (net (code "105") (name "unconnected-(U2B-PQ1-Pad6)") (class "Default")
      (node (ref "U2") (pin "6") (pinfunction "PQ1_6") (pintype "bidirectional+no_connect"))
    )
    (net (code "106") (name "unconnected-(U2B-PQ2-Pad11)") (class "Default")
      (node (ref "U2") (pin "11") (pinfunction "PQ2_11") (pintype "bidirectional+no_connect"))
    )
    (net (code "107") (name "unconnected-(U2B-PQ3-Pad27)") (class "Default")
      (node (ref "U2") (pin "27") (pinfunction "PQ3_27") (pintype "bidirectional+no_connect"))
    )
    (net (code "108") (name "unconnected-(U2B-PQ4-Pad102)") (class "Default")
      (node (ref "U2") (pin "102") (pinfunction "PQ4_102") (pintype "bidirectional+no_connect"))
    )
    (net (code "109") (name "unconnected-(U2C-EN0RXIN-Pad53)") (class "Default")
      (node (ref "U2") (pin "53") (pinfunction "EN0RXIN_53") (pintype "bidirectional+no_connect"))
    )
    (net (code "110") (name "unconnected-(U2C-EN0RXIP-Pad54)") (class "Default")
      (node (ref "U2") (pin "54") (pinfunction "EN0RXIP_54") (pintype "bidirectional+no_connect"))
    )
    (net (code "111") (name "unconnected-(U2C-EN0TXON-Pad56)") (class "Default")
      (node (ref "U2") (pin "56") (pinfunction "EN0TXON_56") (pintype "bidirectional+no_connect"))
    )
    (net (code "112") (name "unconnected-(U2C-EN0TXOP-Pad57)") (class "Default")
      (node (ref "U2") (pin "57") (pinfunction "EN0TXOP_57") (pintype "bidirectional+no_connect"))
    )
    (net (code "113") (name "unconnected-(U2C-HIB-Pad65)") (class "Default")
      (node (ref "U2") (pin "65") (pinfunction "HIB_65") (pintype "output+no_connect"))
    )
    (net (code "114") (name "unconnected-(U2C-XOSC1-Pad67)") (class "Default")
      (node (ref "U2") (pin "67") (pinfunction "XOSC1_67") (pintype "output+no_connect"))
    )
    (net (code "115") (name "unconnected-(U12-IO1-Pad1)") (class "Default")
      (node (ref "U12") (pin "1") (pinfunction "IO1_1") (pintype "passive+no_connect"))
    )
  )
)
